# FTDI.net
KiCad netlist of a schematic drawn in Altium Designer
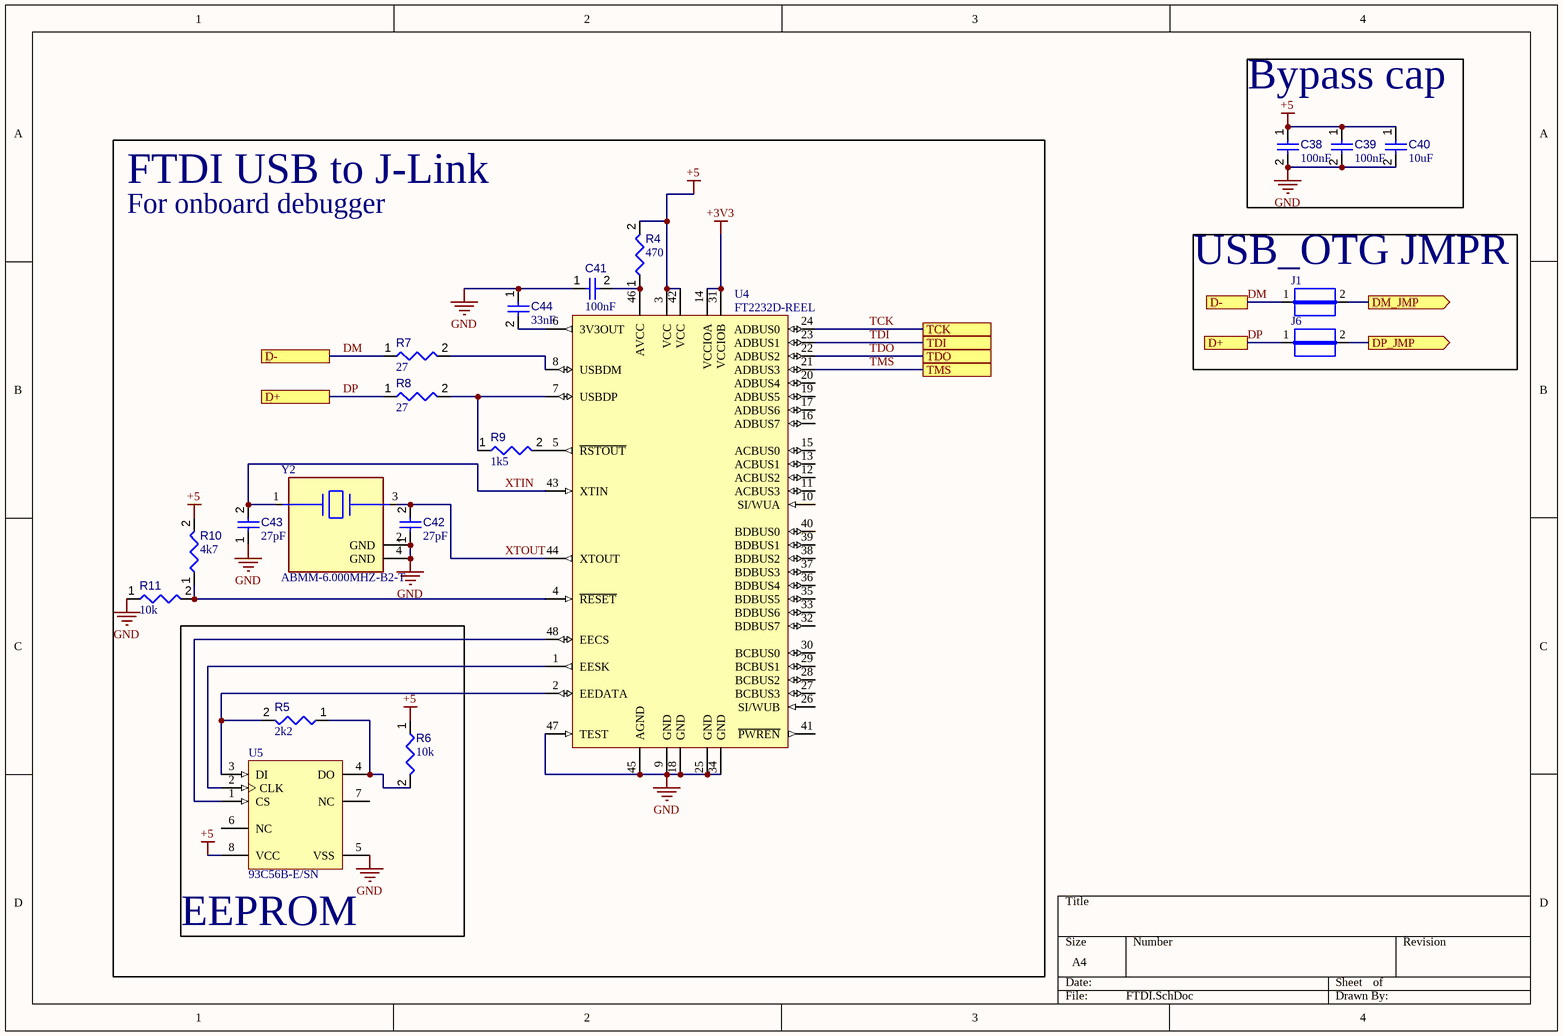
[diagram p0: FTDI.SchDoc]

(export (version "E")
  (design (tool "Eeschema 10.0.6"))
  (components
    (comp (ref "C38")
      (value "100nF")
      (footprint "CAPC0603(1608)100_L")
      (description "Chip Capacitor, 470nF +/-20%, 25V, 0603, Thickness 1 mm")
      (fields (field (name "TOLERANCE") "10%") (field (name "Comment") "Capacitor 470nF +/-20% 25V 0603"))
      (libsource (lib "ESD320") (part "CAP-NP-2"))
    )
    (comp (ref "C39")
      (value "100nF")
      (footprint "CAPC0603(1608)100_L")
      (description "Chip Capacitor, 470nF +/-20%, 25V, 0603, Thickness 1 mm")
      (fields (field (name "TOLERANCE") "10%") (field (name "Comment") "Capacitor 470nF +/-20% 25V 0603"))
      (libsource (lib "ESD320") (part "CAP-NP-2"))
    )
    (comp (ref "C40")
      (value "10uF")
      (footprint "CAPC0603(1608)100_L")
      (description "Chip Capacitor, 470nF +/-20%, 25V, 0603, Thickness 1 mm")
      (fields (field (name "TOLERANCE") "10%") (field (name "Comment") "Capacitor 470nF +/-20% 25V 0603"))
      (libsource (lib "ESD320") (part "CAP-NP-2"))
    )
    (comp (ref "C41")
      (value "100nF")
      (footprint "CAPC0603(1608)100_L")
      (description "Chip Capacitor, 470nF +/-20%, 25V, 0603, Thickness 1 mm")
      (fields (field (name "TOLERANCE") "10%") (field (name "Comment") "Capacitor 470nF +/-20% 25V 0603"))
      (libsource (lib "ESD320") (part "CAP-NP-2"))
    )
    (comp (ref "C42")
      (value "27pF")
      (footprint "CAPC0603(1608)100_L")
      (description "Chip Capacitor, 470nF +/-20%, 25V, 0603, Thickness 1 mm")
      (fields (field (name "TOLERANCE") "10%") (field (name "Comment") "Capacitor 470nF +/-20% 25V 0603"))
      (libsource (lib "ESD320") (part "CAP-NP-2"))
    )
    (comp (ref "C43")
      (value "27pF")
      (footprint "CAPC0603(1608)100_L")
      (description "Chip Capacitor, 470nF +/-20%, 25V, 0603, Thickness 1 mm")
      (fields (field (name "TOLERANCE") "10%") (field (name "Comment") "Capacitor 470nF +/-20% 25V 0603"))
      (libsource (lib "ESD320") (part "CAP-NP-2"))
    )
    (comp (ref "C44")
      (value "33nF")
      (footprint "CAPC0603(1608)100_L")
      (description "Chip Capacitor, 470nF +/-20%, 25V, 0603, Thickness 1 mm")
      (fields (field (name "TOLERANCE") "10%") (field (name "Comment") "Capacitor 470nF +/-20% 25V 0603"))
      (libsource (lib "ESD320") (part "CAP-NP-2"))
    )
    (comp (ref "J1") (value "JUMPER") (footprint "JUMPER") (libsource (lib "ESD320") (part "JUMPER")))
    (comp (ref "J6") (value "JUMPER") (footprint "JUMPER") (libsource (lib "ESD320") (part "JUMPER")))
    (comp (ref "R4")
      (value "470")
      (footprint "RESC0603(1608)_L")
      (description "120R 0.1W 5% 0603 (1608 Metric)  SMD")
      (fields (field (name "POWER") "100mW") (field (name "TOLERANCE") "5%"))
      (libsource (lib "ESD320") (part "120R3J"))
    )
    (comp (ref "R5")
      (value "2k2")
      (footprint "RESC0603(1608)_L")
      (description "120R 0.1W 5% 0603 (1608 Metric)  SMD")
      (fields (field (name "POWER") "100mW") (field (name "TOLERANCE") "5%"))
      (libsource (lib "ESD320") (part "120R3J"))
    )
    (comp (ref "R6")
      (value "10k")
      (footprint "RESC0603(1608)_L")
      (description "120R 0.1W 5% 0603 (1608 Metric)  SMD")
      (fields (field (name "POWER") "100mW") (field (name "TOLERANCE") "5%"))
      (libsource (lib "ESD320") (part "120R3J"))
    )
    (comp (ref "R7")
      (value "27")
      (footprint "RESC0603(1608)_L")
      (description "120R 0.1W 5% 0603 (1608 Metric)  SMD")
      (fields (field (name "POWER") "100mW") (field (name "TOLERANCE") "5%"))
      (libsource (lib "ESD320") (part "120R3J"))
    )
    (comp (ref "R8")
      (value "27")
      (footprint "RESC0603(1608)_L")
      (description "120R 0.1W 5% 0603 (1608 Metric)  SMD")
      (fields (field (name "POWER") "100mW") (field (name "TOLERANCE") "5%"))
      (libsource (lib "ESD320") (part "120R3J"))
    )
    (comp (ref "R9")
      (value "1k5")
      (footprint "RESC0603(1608)_L")
      (description "120R 0.1W 5% 0603 (1608 Metric)  SMD")
      (fields (field (name "POWER") "100mW") (field (name "TOLERANCE") "5%"))
      (libsource (lib "ESD320") (part "120R3J"))
    )
    (comp (ref "R10")
      (value "4k7")
      (footprint "RESC0603(1608)_L")
      (description "120R 0.1W 5% 0603 (1608 Metric)  SMD")
      (fields (field (name "POWER") "100mW") (field (name "TOLERANCE") "5%"))
      (libsource (lib "ESD320") (part "120R3J"))
    )
    (comp (ref "R11")
      (value "10k")
      (footprint "RESC0603(1608)_L")
      (description "120R 0.1W 5% 0603 (1608 Metric)  SMD")
      (fields (field (name "POWER") "100mW") (field (name "TOLERANCE") "5%"))
      (libsource (lib "ESD320") (part "120R3J"))
    )
    (comp (ref "U4")
      (value "FT2232D-REEL")
      (footprint "LQFP-48_L")
      (description "FT2232D Dual USB to Serial UART/FIFO IC, -40 to +85 degC, 48-Pin LQFP, Pb-Free, Tape and Reel")
      (fields (field (name "MANUFACTURER") "FTDI"))
      (libsource (lib "Altium Content Vault") (part "COM-UART-FT2232D-SQ48"))
    )
    (comp (ref "U5")
      (value "93C56B-E/SN")
      (footprint "SOIC-SN8_M")
      (description "2K, 128x16-bit, 5.0V Microwire Serial EEPROM, 8-Pin SOIC 150mil, Extended Temperature")
      (libsource (lib "Altium Content Vault") (part "MEM-SEEPROM-93AA46B-P-8"))
    )
    (comp (ref "Y2")
      (value "ABMM-6.000MHZ-B2-T")
      (footprint "FP-ABMM-MFG")
      (description "CRYSTAL 6.0000MHZ 18PF SMD")
      (fields (field (name "TOLERANCE") "20ppm"))
      (libsource (lib "Altium Content Vault") (part "14e648fd3e94df574add110f4c202a0"))
    )
  )
  (nets
    (net (code "1") (name "+3V3") (class "Default")
      (node (ref "U4") (pin "14") (pinfunction "VCCIOA_14") (pintype "power_in"))
      (node (ref "U4") (pin "31") (pinfunction "VCCIOB_31") (pintype "power_in"))
    )
    (net (code "2") (name "+5") (class "Default")
      (node (ref "C38") (pin "1") (pinfunction "1_1") (pintype "passive"))
      (node (ref "C39") (pin "1") (pinfunction "1_1") (pintype "passive"))
      (node (ref "C40") (pin "1") (pinfunction "1_1") (pintype "passive"))
      (node (ref "R10") (pin "2") (pinfunction "2_2") (pintype "passive"))
      (node (ref "R4") (pin "2") (pinfunction "2_2") (pintype "passive"))
      (node (ref "R6") (pin "1") (pinfunction "1_1") (pintype "passive"))
      (node (ref "U4") (pin "3") (pinfunction "VCC_3") (pintype "power_in"))
      (node (ref "U4") (pin "42") (pinfunction "VCC_42") (pintype "power_in"))
      (node (ref "U5") (pin "8") (pinfunction "VCC_8") (pintype "power_in"))
    )
    (net (code "3") (name "/DM") (class "Default")
      (node (ref "J1") (pin "1") (pinfunction "1_1") (pintype "passive"))
      (node (ref "R7") (pin "1") (pinfunction "1_1") (pintype "passive"))
    )
    (net (code "4") (name "/DM_JMP") (class "Default")
      (node (ref "J1") (pin "2") (pinfunction "2_2") (pintype "passive"))
    )
    (net (code "5") (name "/DP") (class "Default")
      (node (ref "J6") (pin "1") (pinfunction "1_1") (pintype "passive"))
      (node (ref "R8") (pin "1") (pinfunction "1_1") (pintype "passive"))
    )
    (net (code "6") (name "/DP_JMP") (class "Default")
      (node (ref "J6") (pin "2") (pinfunction "2_2") (pintype "passive"))
    )
    (net (code "7") (name "/TCK") (class "Default")
      (node (ref "U4") (pin "24") (pinfunction "ADBUS0_24") (pintype "bidirectional"))
    )
    (net (code "8") (name "/TDI") (class "Default")
      (node (ref "U4") (pin "23") (pinfunction "ADBUS1_23") (pintype "bidirectional"))
    )
    (net (code "9") (name "/TDO") (class "Default")
      (node (ref "U4") (pin "22") (pinfunction "ADBUS2_22") (pintype "bidirectional"))
    )
    (net (code "10") (name "/TMS") (class "Default")
      (node (ref "U4") (pin "21") (pinfunction "ADBUS3_21") (pintype "bidirectional"))
    )
    (net (code "11") (name "/XTIN") (class "Default")
      (node (ref "C43") (pin "2") (pinfunction "2_2") (pintype "passive"))
      (node (ref "U4") (pin "43") (pinfunction "XTIN_43") (pintype "input"))
      (node (ref "Y2") (pin "1") (pinfunction "1_1") (pintype "passive"))
    )
    (net (code "12") (name "/XTOUT") (class "Default")
      (node (ref "C42") (pin "2") (pinfunction "2_2") (pintype "passive"))
      (node (ref "U4") (pin "44") (pinfunction "XTOUT_44") (pintype "output"))
      (node (ref "Y2") (pin "3") (pinfunction "3_3") (pintype "passive"))
    )
    (net (code "13") (name "GND") (class "Default")
      (node (ref "C38") (pin "2") (pinfunction "2_2") (pintype "passive"))
      (node (ref "C39") (pin "2") (pinfunction "2_2") (pintype "passive"))
      (node (ref "C40") (pin "2") (pinfunction "2_2") (pintype "passive"))
      (node (ref "C41") (pin "1") (pinfunction "1_1") (pintype "passive"))
      (node (ref "C42") (pin "1") (pinfunction "1_1") (pintype "passive"))
      (node (ref "C43") (pin "1") (pinfunction "1_1") (pintype "passive"))
      (node (ref "C44") (pin "1") (pinfunction "1_1") (pintype "passive"))
      (node (ref "R11") (pin "1") (pinfunction "1_1") (pintype "passive"))
      (node (ref "U4") (pin "18") (pinfunction "GND_18") (pintype "power_in"))
      (node (ref "U4") (pin "25") (pinfunction "GND_25") (pintype "power_in"))
      (node (ref "U4") (pin "34") (pinfunction "GND_34") (pintype "power_in"))
      (node (ref "U4") (pin "45") (pinfunction "AGND_45") (pintype "power_in"))
      (node (ref "U4") (pin "47") (pinfunction "TEST_47") (pintype "input"))
      (node (ref "U4") (pin "9") (pinfunction "GND_9") (pintype "power_in"))
      (node (ref "U5") (pin "5") (pinfunction "VSS_5") (pintype "power_in"))
      (node (ref "Y2") (pin "2") (pinfunction "GND_2") (pintype "passive"))
      (node (ref "Y2") (pin "4") (pinfunction "GND_4") (pintype "passive"))
    )
    (net (code "14") (name "Net-(U4-3V3OUT)") (class "Default")
      (node (ref "C44") (pin "2") (pinfunction "2_2") (pintype "passive"))
      (node (ref "U4") (pin "6") (pinfunction "3V3OUT_6") (pintype "output"))
    )
    (net (code "15") (name "Net-(U4-AVCC)") (class "Default")
      (node (ref "C41") (pin "2") (pinfunction "2_2") (pintype "passive"))
      (node (ref "R4") (pin "1") (pinfunction "1_1") (pintype "passive"))
      (node (ref "U4") (pin "46") (pinfunction "AVCC_46") (pintype "power_in"))
    )
    (net (code "16") (name "Net-(U4-EECS)") (class "Default")
      (node (ref "U4") (pin "48") (pinfunction "EECS_48") (pintype "bidirectional"))
      (node (ref "U5") (pin "1") (pinfunction "CS_1") (pintype "input"))
    )
    (net (code "17") (name "Net-(U4-EEDATA)") (class "Default")
      (node (ref "R5") (pin "2") (pinfunction "2_2") (pintype "passive"))
      (node (ref "U4") (pin "2") (pinfunction "EEDATA_2") (pintype "bidirectional"))
      (node (ref "U5") (pin "3") (pinfunction "DI_3") (pintype "input"))
    )
    (net (code "18") (name "Net-(U4-EESK)") (class "Default")
      (node (ref "U4") (pin "1") (pinfunction "EESK_1") (pintype "output"))
      (node (ref "U5") (pin "2") (pinfunction "CLK_2") (pintype "input"))
    )
    (net (code "19") (name "Net-(U4-USBDM)") (class "Default")
      (node (ref "R7") (pin "2") (pinfunction "2_2") (pintype "passive"))
      (node (ref "U4") (pin "8") (pinfunction "USBDM_8") (pintype "bidirectional"))
    )
    (net (code "20") (name "Net-(U4-USBDP)") (class "Default")
      (node (ref "R8") (pin "2") (pinfunction "2_2") (pintype "passive"))
      (node (ref "R9") (pin "1") (pinfunction "1_1") (pintype "passive"))
      (node (ref "U4") (pin "7") (pinfunction "USBDP_7") (pintype "bidirectional"))
    )
    (net (code "21") (name "Net-(U4-~{RESET})") (class "Default")
      (node (ref "R10") (pin "1") (pinfunction "1_1") (pintype "passive"))
      (node (ref "R11") (pin "2") (pinfunction "2_2") (pintype "passive"))
      (node (ref "U4") (pin "4") (pinfunction "~{RESET}_4") (pintype "input"))
    )
    (net (code "22") (name "Net-(U4-~{RSTOUT})") (class "Default")
      (node (ref "R9") (pin "2") (pinfunction "2_2") (pintype "passive"))
      (node (ref "U4") (pin "5") (pinfunction "~{RSTOUT}_5") (pintype "output"))
    )
    (net (code "23") (name "Net-(U5-DO)") (class "Default")
      (node (ref "R5") (pin "1") (pinfunction "1_1") (pintype "passive"))
      (node (ref "R6") (pin "2") (pinfunction "2_2") (pintype "passive"))
      (node (ref "U5") (pin "4") (pinfunction "DO_4") (pintype "tri_state"))
    )
    (net (code "24") (name "unconnected-(U4-ACBUS0-Pad15)") (class "Default")
      (node (ref "U4") (pin "15") (pinfunction "ACBUS0_15") (pintype "bidirectional"))
    )
    (net (code "25") (name "unconnected-(U4-ACBUS1-Pad13)") (class "Default")
      (node (ref "U4") (pin "13") (pinfunction "ACBUS1_13") (pintype "bidirectional"))
    )
    (net (code "26") (name "unconnected-(U4-ACBUS2-Pad12)") (class "Default")
      (node (ref "U4") (pin "12") (pinfunction "ACBUS2_12") (pintype "bidirectional"))
    )
    (net (code "27") (name "unconnected-(U4-ACBUS3-Pad11)") (class "Default")
      (node (ref "U4") (pin "11") (pinfunction "ACBUS3_11") (pintype "bidirectional"))
    )
    (net (code "28") (name "unconnected-(U4-ADBUS4-Pad20)") (class "Default")
      (node (ref "U4") (pin "20") (pinfunction "ADBUS4_20") (pintype "bidirectional"))
    )
    (net (code "29") (name "unconnected-(U4-ADBUS5-Pad19)") (class "Default")
      (node (ref "U4") (pin "19") (pinfunction "ADBUS5_19") (pintype "bidirectional"))
    )
    (net (code "30") (name "unconnected-(U4-ADBUS6-Pad17)") (class "Default")
      (node (ref "U4") (pin "17") (pinfunction "ADBUS6_17") (pintype "bidirectional"))
    )
    (net (code "31") (name "unconnected-(U4-ADBUS7-Pad16)") (class "Default")
      (node (ref "U4") (pin "16") (pinfunction "ADBUS7_16") (pintype "bidirectional"))
    )
    (net (code "32") (name "unconnected-(U4-BCBUS0-Pad30)") (class "Default")
      (node (ref "U4") (pin "30") (pinfunction "BCBUS0_30") (pintype "bidirectional"))
    )
    (net (code "33") (name "unconnected-(U4-BCBUS1-Pad29)") (class "Default")
      (node (ref "U4") (pin "29") (pinfunction "BCBUS1_29") (pintype "bidirectional"))
    )
    (net (code "34") (name "unconnected-(U4-BCBUS2-Pad28)") (class "Default")
      (node (ref "U4") (pin "28") (pinfunction "BCBUS2_28") (pintype "bidirectional"))
    )
    (net (code "35") (name "unconnected-(U4-BCBUS3-Pad27)") (class "Default")
      (node (ref "U4") (pin "27") (pinfunction "BCBUS3_27") (pintype "bidirectional"))
    )
    (net (code "36") (name "unconnected-(U4-BDBUS0-Pad40)") (class "Default")
      (node (ref "U4") (pin "40") (pinfunction "BDBUS0_40") (pintype "bidirectional"))
    )
    (net (code "37") (name "unconnected-(U4-BDBUS1-Pad39)") (class "Default")
      (node (ref "U4") (pin "39") (pinfunction "BDBUS1_39") (pintype "bidirectional"))
    )
    (net (code "38") (name "unconnected-(U4-BDBUS2-Pad38)") (class "Default")
      (node (ref "U4") (pin "38") (pinfunction "BDBUS2_38") (pintype "bidirectional"))
    )
    (net (code "39") (name "unconnected-(U4-BDBUS3-Pad37)") (class "Default")
      (node (ref "U4") (pin "37") (pinfunction "BDBUS3_37") (pintype "bidirectional"))
    )
    (net (code "40") (name "unconnected-(U4-BDBUS4-Pad36)") (class "Default")
      (node (ref "U4") (pin "36") (pinfunction "BDBUS4_36") (pintype "bidirectional"))
    )
    (net (code "41") (name "unconnected-(U4-BDBUS5-Pad35)") (class "Default")
      (node (ref "U4") (pin "35") (pinfunction "BDBUS5_35") (pintype "bidirectional"))
    )
    (net (code "42") (name "unconnected-(U4-BDBUS6-Pad33)") (class "Default")
      (node (ref "U4") (pin "33") (pinfunction "BDBUS6_33") (pintype "bidirectional"))
    )
    (net (code "43") (name "unconnected-(U4-BDBUS7-Pad32)") (class "Default")
      (node (ref "U4") (pin "32") (pinfunction "BDBUS7_32") (pintype "bidirectional"))
    )
    (net (code "44") (name "unconnected-(U4-SI{slash}WUA-Pad10)") (class "Default")
      (node (ref "U4") (pin "10") (pinfunction "SI/WUA_10") (pintype "input"))
    )
    (net (code "45") (name "unconnected-(U4-SI{slash}WUB-Pad26)") (class "Default")
      (node (ref "U4") (pin "26") (pinfunction "SI/WUB_26") (pintype "input"))
    )
    (net (code "46") (name "unconnected-(U4-~{PWREN}-Pad41)") (class "Default")
      (node (ref "U4") (pin "41") (pinfunction "~{PWREN}_41") (pintype "output"))
    )
    (net (code "47") (name "unconnected-(U5-NC-Pad6)") (class "Default")
      (node (ref "U5") (pin "6") (pinfunction "NC_6") (pintype "passive"))
    )
    (net (code "48") (name "unconnected-(U5-NC-Pad7)") (class "Default")
      (node (ref "U5") (pin "7") (pinfunction "NC_7") (pintype "passive"))
    )
  )
)
